# Driver_Screen_Board.net
KiCad netlist of a schematic drawn in EAGLE
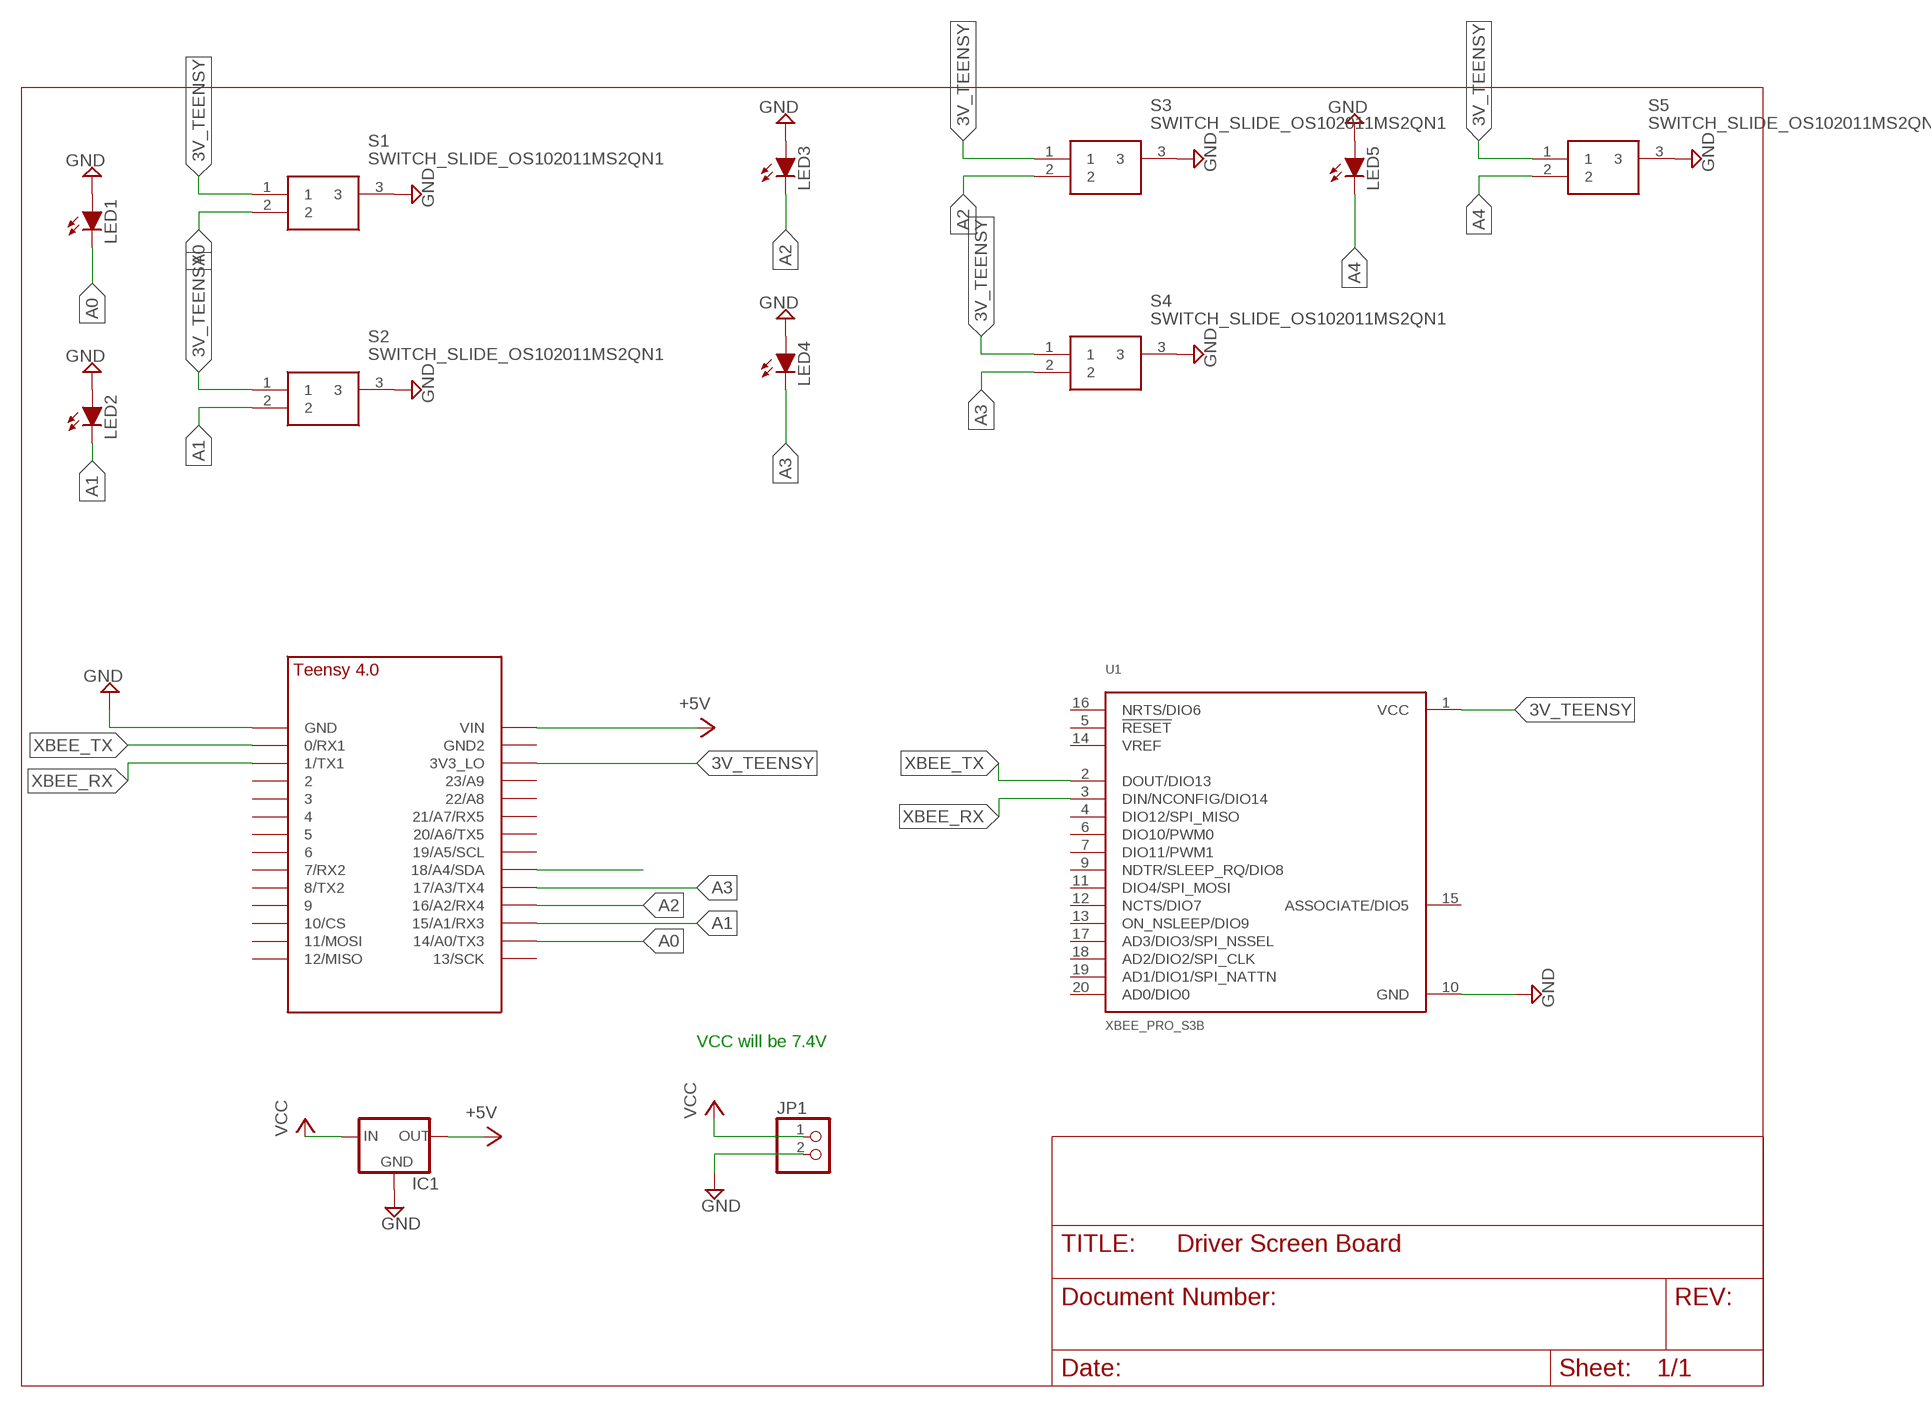
[diagram p0: schematic, sheet 1]

(export (version "E")
  (design (tool "Eeschema 10.0.6"))
  (components
    (comp (ref "IC1")
      (value "REG_5V_L7805_HOR_HOLE")
      (footprint "eagle-import:TO-220-H-HOLE")
      (libsource (lib "eagle-import") (part "REG_5V_L7805_HOR_HOLE"))
    )
    (comp (ref "JP1")
      (value "PINHD-1X2")
      (footprint "eagle-import:1X02")
      (libsource (lib "eagle-import") (part "PINHD-1X2"))
    )
    (comp (ref "LED1")
      (value "LED-5MM")
      (footprint "eagle-import:LED-5MM")
      (libsource (lib "eagle-import") (part "LED-5MM"))
    )
    (comp (ref "LED2")
      (value "LED-5MM")
      (footprint "eagle-import:LED-5MM")
      (libsource (lib "eagle-import") (part "LED-5MM"))
    )
    (comp (ref "LED3")
      (value "LED-5MM")
      (footprint "eagle-import:LED-5MM")
      (libsource (lib "eagle-import") (part "LED-5MM"))
    )
    (comp (ref "LED4")
      (value "LED-5MM")
      (footprint "eagle-import:LED-5MM")
      (libsource (lib "eagle-import") (part "LED-5MM"))
    )
    (comp (ref "LED5")
      (value "LED-5MM")
      (footprint "eagle-import:LED-5MM")
      (libsource (lib "eagle-import") (part "LED-5MM"))
    )
    (comp (ref "S1")
      (value "SWITCH_SLIDE_OS102011MS2QN1")
      (footprint "eagle-import:OS102011MA1QN1")
      (fields
        (field (name "ARROW_PART_NUMBER") "OS102011MS2QN1")
        (field (name "MOUSER_PART_NUMBER") "611-OS102011MS2QN1")
      )
      (libsource (lib "eagle-import") (part "SWITCH_SLIDE_OS102011MS2QN1"))
    )
    (comp (ref "S2")
      (value "SWITCH_SLIDE_OS102011MS2QN1")
      (footprint "eagle-import:OS102011MA1QN1")
      (fields
        (field (name "ARROW_PART_NUMBER") "OS102011MS2QN1")
        (field (name "MOUSER_PART_NUMBER") "611-OS102011MS2QN1")
      )
      (libsource (lib "eagle-import") (part "SWITCH_SLIDE_OS102011MS2QN1"))
    )
    (comp (ref "S3")
      (value "SWITCH_SLIDE_OS102011MS2QN1")
      (footprint "eagle-import:OS102011MA1QN1")
      (fields
        (field (name "ARROW_PART_NUMBER") "OS102011MS2QN1")
        (field (name "MOUSER_PART_NUMBER") "611-OS102011MS2QN1")
      )
      (libsource (lib "eagle-import") (part "SWITCH_SLIDE_OS102011MS2QN1"))
    )
    (comp (ref "S4")
      (value "SWITCH_SLIDE_OS102011MS2QN1")
      (footprint "eagle-import:OS102011MA1QN1")
      (fields
        (field (name "ARROW_PART_NUMBER") "OS102011MS2QN1")
        (field (name "MOUSER_PART_NUMBER") "611-OS102011MS2QN1")
      )
      (libsource (lib "eagle-import") (part "SWITCH_SLIDE_OS102011MS2QN1"))
    )
    (comp (ref "S5")
      (value "SWITCH_SLIDE_OS102011MS2QN1")
      (footprint "eagle-import:OS102011MA1QN1")
      (fields
        (field (name "ARROW_PART_NUMBER") "OS102011MS2QN1")
        (field (name "MOUSER_PART_NUMBER") "611-OS102011MS2QN1")
      )
      (libsource (lib "eagle-import") (part "SWITCH_SLIDE_OS102011MS2QN1"))
    )
    (comp (ref "U$1")
      (value "TEENSY_4.0_SIMPLE")
      (footprint "eagle-import:TEENSY_4.0_SIMPLE")
      (libsource (lib "eagle-import") (part "TEENSY_4.0_SIMPLE"))
    )
    (comp (ref "U1")
      (value "XBEE_PRO_S3B")
      (footprint "eagle-import:XBEE_PRO_S3B")
      (fields
        (field (name "DIGI-KEY_PART_NUMBER") "602-1293-ND")
        (field (name "MF") "Digi International")
        (field (name "MP") "XBP9B-XCST-001")
      )
      (libsource (lib "eagle-import") (part "XBEE_PRO_S3B"))
    )
  )
  (nets
    (net (code "1") (name "+5V") (class "Default")
      (node (ref "IC1") (pin "3") (pinfunction "OUT_3") (pintype "output"))
      (node (ref "U$1") (pin "VIN") (pinfunction "VIN_VIN") (pintype "bidirectional"))
    )
    (net (code "2") (name "3V_TEENSY") (class "Default")
      (node (ref "S1") (pin "1") (pinfunction "1_1") (pintype "bidirectional"))
      (node (ref "S2") (pin "1") (pinfunction "1_1") (pintype "bidirectional"))
      (node (ref "S3") (pin "1") (pinfunction "1_1") (pintype "bidirectional"))
      (node (ref "S4") (pin "1") (pinfunction "1_1") (pintype "bidirectional"))
      (node (ref "S5") (pin "1") (pinfunction "1_1") (pintype "bidirectional"))
      (node (ref "U$1") (pin "3V3_LO") (pinfunction "3V3_LO_3V3_LO") (pintype "bidirectional"))
      (node (ref "U1") (pin "1") (pinfunction "VCC_1") (pintype "power_in"))
    )
    (net (code "3") (name "A0") (class "Default")
      (node (ref "LED1") (pin "K") (pinfunction "C_K") (pintype "passive"))
      (node (ref "S1") (pin "2") (pinfunction "2_2") (pintype "bidirectional"))
      (node (ref "U$1") (pin "14/A0") (pinfunction "14/A0/TX3_14/A0") (pintype "bidirectional"))
    )
    (net (code "4") (name "A1") (class "Default")
      (node (ref "LED2") (pin "K") (pinfunction "C_K") (pintype "passive"))
      (node (ref "S2") (pin "2") (pinfunction "2_2") (pintype "bidirectional"))
      (node (ref "U$1") (pin "15/A1") (pinfunction "15/A1/RX3_15/A1") (pintype "bidirectional"))
    )
    (net (code "5") (name "A2") (class "Default")
      (node (ref "LED3") (pin "K") (pinfunction "C_K") (pintype "passive"))
      (node (ref "S3") (pin "2") (pinfunction "2_2") (pintype "bidirectional"))
      (node (ref "U$1") (pin "16/A2") (pinfunction "16/A2/RX4_16/A2") (pintype "bidirectional"))
    )
    (net (code "6") (name "A3") (class "Default")
      (node (ref "LED4") (pin "K") (pinfunction "C_K") (pintype "passive"))
      (node (ref "S4") (pin "2") (pinfunction "2_2") (pintype "bidirectional"))
      (node (ref "U$1") (pin "17/A3") (pinfunction "17/A3/TX4_17/A3") (pintype "bidirectional"))
    )
    (net (code "7") (name "A4") (class "Default")
      (node (ref "LED5") (pin "K") (pinfunction "C_K") (pintype "passive"))
      (node (ref "S5") (pin "2") (pinfunction "2_2") (pintype "bidirectional"))
      (node (ref "U$1") (pin "18/A4/SDA") (pinfunction "18/A4/SDA_18/A4/SDA") (pintype "bidirectional"))
    )
    (net (code "8") (name "GND") (class "Default")
      (node (ref "IC1") (pin "2") (pinfunction "GND_2") (pintype "input"))
      (node (ref "JP1") (pin "2") (pinfunction "2_2") (pintype "passive"))
      (node (ref "LED1") (pin "A") (pinfunction "A_A") (pintype "passive"))
      (node (ref "LED2") (pin "A") (pinfunction "A_A") (pintype "passive"))
      (node (ref "LED3") (pin "A") (pinfunction "A_A") (pintype "passive"))
      (node (ref "LED4") (pin "A") (pinfunction "A_A") (pintype "passive"))
      (node (ref "LED5") (pin "A") (pinfunction "A_A") (pintype "passive"))
      (node (ref "S1") (pin "3") (pinfunction "3_3") (pintype "bidirectional"))
      (node (ref "S2") (pin "3") (pinfunction "3_3") (pintype "bidirectional"))
      (node (ref "S3") (pin "3") (pinfunction "3_3") (pintype "bidirectional"))
      (node (ref "S4") (pin "3") (pinfunction "3_3") (pintype "bidirectional"))
      (node (ref "S5") (pin "3") (pinfunction "3_3") (pintype "bidirectional"))
      (node (ref "U$1") (pin "GND") (pinfunction "GND_GND") (pintype "bidirectional"))
      (node (ref "U1") (pin "10") (pinfunction "GND_10") (pintype "power_in"))
    )
    (net (code "9") (name "VCC") (class "Default")
      (node (ref "IC1") (pin "1") (pinfunction "IN_1") (pintype "input"))
      (node (ref "JP1") (pin "1") (pinfunction "1_1") (pintype "passive"))
    )
    (net (code "10") (name "XBEE_RX") (class "Default")
      (node (ref "U$1") (pin "1/TX") (pinfunction "1/TX1_1/TX") (pintype "bidirectional"))
      (node (ref "U1") (pin "3") (pinfunction "DIN/NCONFIG/DIO14_3") (pintype "bidirectional"))
    )
    (net (code "11") (name "XBEE_TX") (class "Default")
      (node (ref "U$1") (pin "0/RX") (pinfunction "0/RX1_0/RX") (pintype "bidirectional"))
      (node (ref "U1") (pin "2") (pinfunction "DOUT/DIO13_2") (pintype "bidirectional"))
    )
    (net (code "12") (name "unconnected-(U$1-3-Pad3{slash}CANTX)") (class "Default")
      (node (ref "U$1") (pin "3/CANTX") (pinfunction "3_3/CANTX") (pintype "bidirectional"))
    )
    (net (code "13") (name "unconnected-(U$1-4-Pad4{slash}CANRX)") (class "Default")
      (node (ref "U$1") (pin "4/CANRX") (pinfunction "4_4/CANRX") (pintype "bidirectional"))
    )
    (net (code "14") (name "unconnected-(U$1-7{slash}RX2-Pad7)") (class "Default")
      (node (ref "U$1") (pin "7") (pinfunction "7/RX2_7") (pintype "bidirectional"))
    )
    (net (code "15") (name "unconnected-(U$1-8{slash}TX2-Pad8)") (class "Default")
      (node (ref "U$1") (pin "8") (pinfunction "8/TX2_8") (pintype "bidirectional"))
    )
    (net (code "16") (name "unconnected-(U$1-9-Pad9{slash}CS)") (class "Default")
      (node (ref "U$1") (pin "9/CS") (pinfunction "9_9/CS") (pintype "bidirectional"))
    )
    (net (code "17") (name "unconnected-(U$1-20{slash}A6{slash}TX5-Pad20{slash}A6)") (class "Default")
      (node (ref "U$1") (pin "20/A6") (pinfunction "20/A6/TX5_20/A6") (pintype "bidirectional"))
    )
    (net (code "18") (name "unconnected-(U$1-21{slash}A7{slash}RX5-Pad21{slash}A7)") (class "Default")
      (node (ref "U$1") (pin "21/A7") (pinfunction "21/A7/RX5_21/A7") (pintype "bidirectional"))
    )
    (net (code "19") (name "unconnected-(U$1-Pad2)") (class "Default")
      (node (ref "U$1") (pin "2") (pinfunction "2_2") (pintype "bidirectional"))
    )
    (net (code "20") (name "unconnected-(U$1-Pad5)") (class "Default")
      (node (ref "U$1") (pin "5") (pinfunction "5_5") (pintype "bidirectional"))
    )
    (net (code "21") (name "unconnected-(U$1-Pad6)") (class "Default")
      (node (ref "U$1") (pin "6") (pinfunction "6_6") (pintype "bidirectional"))
    )
    (net (code "22") (name "unconnected-(U$1-Pad10{slash}CS)") (class "Default")
      (node (ref "U$1") (pin "10/CS") (pinfunction "10/CS_10/CS") (pintype "bidirectional"))
    )
    (net (code "23") (name "unconnected-(U$1-Pad11{slash}MOSI)") (class "Default")
      (node (ref "U$1") (pin "11/MOSI") (pinfunction "11/MOSI_11/MOSI") (pintype "bidirectional"))
    )
    (net (code "24") (name "unconnected-(U$1-Pad12{slash}MISO)") (class "Default")
      (node (ref "U$1") (pin "12/MISO") (pinfunction "12/MISO_12/MISO") (pintype "bidirectional"))
    )
    (net (code "25") (name "unconnected-(U$1-Pad13{slash}SCK)") (class "Default")
      (node (ref "U$1") (pin "13/SCK") (pinfunction "13/SCK_13/SCK") (pintype "bidirectional"))
    )
    (net (code "26") (name "unconnected-(U$1-Pad19{slash}A5{slash}SCL)") (class "Default")
      (node (ref "U$1") (pin "19/A5/SCL") (pinfunction "19/A5/SCL_19/A5/SCL") (pintype "bidirectional"))
    )
    (net (code "27") (name "unconnected-(U$1-Pad22{slash}A8)") (class "Default")
      (node (ref "U$1") (pin "22/A8") (pinfunction "22/A8_22/A8") (pintype "bidirectional"))
    )
    (net (code "28") (name "unconnected-(U$1-Pad23{slash}A9)") (class "Default")
      (node (ref "U$1") (pin "23/A9") (pinfunction "23/A9_23/A9") (pintype "bidirectional"))
    )
    (net (code "29") (name "unconnected-(U$1-PadGND2)") (class "Default")
      (node (ref "U$1") (pin "GND2") (pinfunction "GND2_GND2") (pintype "bidirectional"))
    )
    (net (code "30") (name "unconnected-(U1-AD0{slash}DIO0-Pad20)") (class "Default")
      (node (ref "U1") (pin "20") (pinfunction "AD0/DIO0_20") (pintype "bidirectional"))
    )
    (net (code "31") (name "unconnected-(U1-AD1{slash}DIO1{slash}SPI_NATTN-Pad19)") (class "Default")
      (node (ref "U1") (pin "19") (pinfunction "AD1/DIO1/SPI_NATTN_19") (pintype "bidirectional"))
    )
    (net (code "32") (name "unconnected-(U1-AD2{slash}DIO2{slash}SPI_CLK-Pad18)") (class "Default")
      (node (ref "U1") (pin "18") (pinfunction "AD2/DIO2/SPI_CLK_18") (pintype "bidirectional"))
    )
    (net (code "33") (name "unconnected-(U1-AD3{slash}DIO3{slash}SPI_NSSEL-Pad17)") (class "Default")
      (node (ref "U1") (pin "17") (pinfunction "AD3/DIO3/SPI_NSSEL_17") (pintype "bidirectional"))
    )
    (net (code "34") (name "unconnected-(U1-ASSOCIATE{slash}DIO5-Pad15)") (class "Default")
      (node (ref "U1") (pin "15") (pinfunction "ASSOCIATE/DIO5_15") (pintype "output"))
    )
    (net (code "35") (name "unconnected-(U1-DIO4{slash}SPI_MOSI-Pad11)") (class "Default")
      (node (ref "U1") (pin "11") (pinfunction "DIO4/SPI_MOSI_11") (pintype "bidirectional"))
    )
    (net (code "36") (name "unconnected-(U1-DIO10{slash}PWM0-Pad6)") (class "Default")
      (node (ref "U1") (pin "6") (pinfunction "DIO10/PWM0_6") (pintype "bidirectional"))
    )
    (net (code "37") (name "unconnected-(U1-DIO11{slash}PWM1-Pad7)") (class "Default")
      (node (ref "U1") (pin "7") (pinfunction "DIO11/PWM1_7") (pintype "bidirectional"))
    )
    (net (code "38") (name "unconnected-(U1-DIO12{slash}SPI_MISO-Pad4)") (class "Default")
      (node (ref "U1") (pin "4") (pinfunction "DIO12/SPI_MISO_4") (pintype "bidirectional"))
    )
    (net (code "39") (name "unconnected-(U1-NCTS{slash}DIO7-Pad12)") (class "Default")
      (node (ref "U1") (pin "12") (pinfunction "NCTS/DIO7_12") (pintype "bidirectional"))
    )
    (net (code "40") (name "unconnected-(U1-NDTR{slash}SLEEP_RQ{slash}DIO8-Pad9)") (class "Default")
      (node (ref "U1") (pin "9") (pinfunction "NDTR/SLEEP_RQ/DIO8_9") (pintype "bidirectional"))
    )
    (net (code "41") (name "unconnected-(U1-NRTS{slash}DIO6-Pad16)") (class "Default")
      (node (ref "U1") (pin "16") (pinfunction "NRTS/DIO6_16") (pintype "input"))
    )
    (net (code "42") (name "unconnected-(U1-ON_NSLEEP{slash}DIO9-Pad13)") (class "Default")
      (node (ref "U1") (pin "13") (pinfunction "ON_NSLEEP/DIO9_13") (pintype "bidirectional"))
    )
    (net (code "43") (name "unconnected-(U1-VREF-Pad14)") (class "Default")
      (node (ref "U1") (pin "14") (pinfunction "VREF_14") (pintype "input"))
    )
    (net (code "44") (name "unconnected-(U1-~{RESET}-Pad5)") (class "Default")
      (node (ref "U1") (pin "5") (pinfunction "~{RESET}_5") (pintype "input"))
    )
  )
)
